# Secondary_MCU_Lidar_Robot.net
KiCad netlist of a schematic drawn in Altium Designer
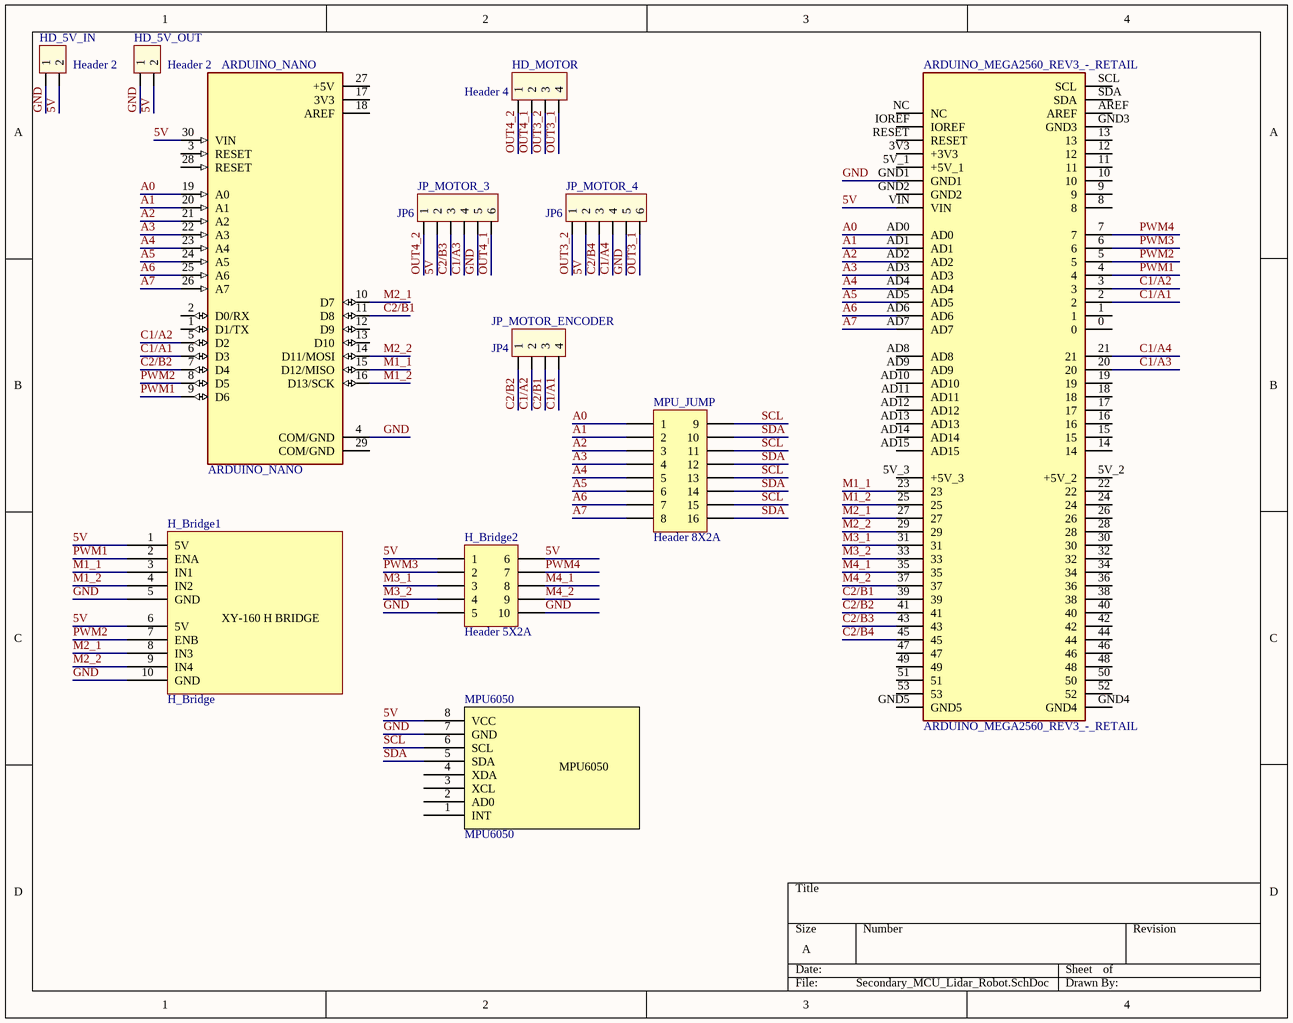
[diagram p0: Secondary_MCU_Lidar_Robot.SchDoc]

(export (version "E")
  (design (tool "Eeschema 10.0.6"))
  (components
    (comp (ref "ARDUINO_MEGA2560_REV3_-_RETAIL")
      (value "ARDUINO_MEGA2560_REV3_-_RETAIL")
      (footprint "ARDUINO_MEGA2560_REV3_-_RETAIL")
      (description "Dev.kit: Arduino; SPI, TWI, UART; ICSP, USB B, pin strips, supply")
      (fields (field (name "MF") "Arduino") (field (name "MP") "ARDUINO MEGA2560 REV3 - RETAIL"))
      (libsource (lib "ARDUINO_MEGA2560_REV3_-_RETAIL") (part "ARDUINO_MEGA2560_REV3_-_RETAIL"))
    )
    (comp (ref "ARDUINO_NANO")
      (value "ARDUINO_NANO")
      (footprint "SHIELD_ARDUINO_NANO")
      (description "ATSAMD21G18A Arduino Nano 33 IoT SAM D ARMÂ® CortexÂ®-M0+ MCU 32-Bit Embedded Evaluation Board")
      (fields (field (name "MP") "ARDUINO NANO") (field (name "MF") "Arduino"))
      (libsource (lib "ARDUINO_NANO") (part "ARDUINO_NANO"))
    )
    (comp (ref "HD_5V_IN")
      (value "Header 2")
      (footprint "HED2T")
      (description "Header 2 (Green)")
      (libsource (lib "syhaunguyen") (part "Hed2"))
    )
    (comp (ref "HD_5V_OUT")
      (value "Header 2")
      (footprint "HED2T")
      (description "Header 2 (Green)")
      (libsource (lib "syhaunguyen") (part "Hed2"))
    )
    (comp (ref "HD_MOTOR")
      (value "Header 4")
      (footprint "HED4T")
      (description "Header 4 (Green)")
      (libsource (lib "syhaunguyen") (part "Hed4"))
    )
    (comp (ref "H_Bridge1")
      (value "H_Bridge")
      (footprint "XY-160D")
      (libsource (lib "Module") (part "Driver H Bridge XY160D"))
    )
    (comp (ref "H_Bridge2")
      (value "Header 5X2A")
      (footprint "HDR2X5_CEN")
      (description "Header, 5-Pin, Dual row")
      (fields (field (name "PUBLISHER") "Altium Limited"))
      (libsource (lib "My library altium") (part "Header 5X2A"))
    )
    (comp (ref "JP_MOTOR_3")
      (value "JP6")
      (footprint "CON6")
      (description "Connector 6")
      (libsource (lib "syhaunguyen") (part "Con6"))
    )
    (comp (ref "JP_MOTOR_4")
      (value "JP6")
      (footprint "CON6")
      (description "Connector 6")
      (libsource (lib "syhaunguyen") (part "Con6"))
    )
    (comp (ref "JP_MOTOR_ENCODER")
      (value "JP4")
      (footprint "CON4")
      (description "Connector 4")
      (libsource (lib "syhaunguyen") (part "Con4"))
    )
    (comp (ref "MPU6050") (value "MPU6050") (footprint "MPU6050") (libsource (lib "Module") (part "MPU6050")))
    (comp (ref "MPU_JUMP")
      (value "Header 8X2A")
      (footprint "HDR2X8_CEN")
      (description "Header, 8-Pin, Dual row")
      (fields (field (name "PUBLISHER") "Altium Limited"))
      (libsource (lib "My library altium") (part "Header 8X2A"))
    )
  )
  (nets
    (net (code "1") (name "/5V") (class "Default")
      (node (ref "ARDUINO_MEGA2560_REV3_-_RETAIL") (pin "VIN") (pinfunction "VIN_VIN") (pintype "passive"))
      (node (ref "ARDUINO_NANO") (pin "30") (pinfunction "VIN_30") (pintype "input"))
      (node (ref "HD_5V_IN") (pin "2") (pinfunction "2_2") (pintype "passive"))
      (node (ref "HD_5V_OUT") (pin "2") (pinfunction "2_2") (pintype "passive"))
      (node (ref "H_Bridge1") (pin "1") (pinfunction "5V_1") (pintype "passive"))
      (node (ref "H_Bridge1") (pin "6") (pinfunction "5V_6") (pintype "passive"))
      (node (ref "H_Bridge2") (pin "1") (pinfunction "1_1") (pintype "passive"))
      (node (ref "H_Bridge2") (pin "6") (pinfunction "6_6") (pintype "passive"))
      (node (ref "JP_MOTOR_3") (pin "2") (pinfunction "2_2") (pintype "passive"))
      (node (ref "JP_MOTOR_4") (pin "2") (pinfunction "2_2") (pintype "passive"))
      (node (ref "MPU6050") (pin "8") (pinfunction "VCC_8") (pintype "passive"))
    )
    (net (code "2") (name "/A0") (class "Default")
      (node (ref "ARDUINO_MEGA2560_REV3_-_RETAIL") (pin "AD0") (pinfunction "AD0_AD0") (pintype "passive"))
      (node (ref "ARDUINO_NANO") (pin "19") (pinfunction "A0_19") (pintype "input"))
      (node (ref "MPU_JUMP") (pin "1") (pinfunction "1_1") (pintype "passive"))
    )
    (net (code "3") (name "/A1") (class "Default")
      (node (ref "ARDUINO_MEGA2560_REV3_-_RETAIL") (pin "AD1") (pinfunction "AD1_AD1") (pintype "passive"))
      (node (ref "ARDUINO_NANO") (pin "20") (pinfunction "A1_20") (pintype "input"))
      (node (ref "MPU_JUMP") (pin "2") (pinfunction "2_2") (pintype "passive"))
    )
    (net (code "4") (name "/A2") (class "Default")
      (node (ref "ARDUINO_MEGA2560_REV3_-_RETAIL") (pin "AD2") (pinfunction "AD2_AD2") (pintype "passive"))
      (node (ref "ARDUINO_NANO") (pin "21") (pinfunction "A2_21") (pintype "input"))
      (node (ref "MPU_JUMP") (pin "3") (pinfunction "3_3") (pintype "passive"))
    )
    (net (code "5") (name "/A3") (class "Default")
      (node (ref "ARDUINO_MEGA2560_REV3_-_RETAIL") (pin "AD3") (pinfunction "AD3_AD3") (pintype "passive"))
      (node (ref "ARDUINO_NANO") (pin "22") (pinfunction "A3_22") (pintype "input"))
      (node (ref "MPU_JUMP") (pin "4") (pinfunction "4_4") (pintype "passive"))
    )
    (net (code "6") (name "/A4") (class "Default")
      (node (ref "ARDUINO_MEGA2560_REV3_-_RETAIL") (pin "AD4") (pinfunction "AD4_AD4") (pintype "passive"))
      (node (ref "ARDUINO_NANO") (pin "23") (pinfunction "A4_23") (pintype "input"))
      (node (ref "MPU_JUMP") (pin "5") (pinfunction "5_5") (pintype "passive"))
    )
    (net (code "7") (name "/A5") (class "Default")
      (node (ref "ARDUINO_MEGA2560_REV3_-_RETAIL") (pin "AD5") (pinfunction "AD5_AD5") (pintype "passive"))
      (node (ref "ARDUINO_NANO") (pin "24") (pinfunction "A5_24") (pintype "input"))
      (node (ref "MPU_JUMP") (pin "6") (pinfunction "6_6") (pintype "passive"))
    )
    (net (code "8") (name "/A6") (class "Default")
      (node (ref "ARDUINO_MEGA2560_REV3_-_RETAIL") (pin "AD6") (pinfunction "AD6_AD6") (pintype "passive"))
      (node (ref "ARDUINO_NANO") (pin "25") (pinfunction "A6_25") (pintype "input"))
      (node (ref "MPU_JUMP") (pin "7") (pinfunction "7_7") (pintype "passive"))
    )
    (net (code "9") (name "/A7") (class "Default")
      (node (ref "ARDUINO_MEGA2560_REV3_-_RETAIL") (pin "AD7") (pinfunction "AD7_AD7") (pintype "passive"))
      (node (ref "ARDUINO_NANO") (pin "26") (pinfunction "A7_26") (pintype "input"))
      (node (ref "MPU_JUMP") (pin "8") (pinfunction "8_8") (pintype "passive"))
    )
    (net (code "10") (name "/C1{slash}A1") (class "Default")
      (node (ref "ARDUINO_MEGA2560_REV3_-_RETAIL") (pin "2") (pinfunction "2_2") (pintype "passive"))
      (node (ref "ARDUINO_NANO") (pin "6") (pinfunction "D3_6") (pintype "bidirectional"))
      (node (ref "JP_MOTOR_ENCODER") (pin "4") (pinfunction "4_4") (pintype "passive"))
    )
    (net (code "11") (name "/C1{slash}A2") (class "Default")
      (node (ref "ARDUINO_MEGA2560_REV3_-_RETAIL") (pin "3") (pinfunction "3_3") (pintype "passive"))
      (node (ref "ARDUINO_NANO") (pin "5") (pinfunction "D2_5") (pintype "bidirectional"))
      (node (ref "JP_MOTOR_ENCODER") (pin "2") (pinfunction "2_2") (pintype "passive"))
    )
    (net (code "12") (name "/C1{slash}A3") (class "Default")
      (node (ref "ARDUINO_MEGA2560_REV3_-_RETAIL") (pin "20") (pinfunction "20_20") (pintype "passive"))
      (node (ref "JP_MOTOR_3") (pin "4") (pinfunction "4_4") (pintype "passive"))
    )
    (net (code "13") (name "/C1{slash}A4") (class "Default")
      (node (ref "ARDUINO_MEGA2560_REV3_-_RETAIL") (pin "21") (pinfunction "21_21") (pintype "passive"))
      (node (ref "JP_MOTOR_4") (pin "4") (pinfunction "4_4") (pintype "passive"))
    )
    (net (code "14") (name "/C2{slash}B1") (class "Default")
      (node (ref "ARDUINO_MEGA2560_REV3_-_RETAIL") (pin "39") (pinfunction "39_39") (pintype "passive"))
      (node (ref "ARDUINO_NANO") (pin "11") (pinfunction "D8_11") (pintype "bidirectional"))
      (node (ref "JP_MOTOR_ENCODER") (pin "3") (pinfunction "3_3") (pintype "passive"))
    )
    (net (code "15") (name "/C2{slash}B2") (class "Default")
      (node (ref "ARDUINO_MEGA2560_REV3_-_RETAIL") (pin "41") (pinfunction "41_41") (pintype "passive"))
      (node (ref "ARDUINO_NANO") (pin "7") (pinfunction "D4_7") (pintype "bidirectional"))
      (node (ref "JP_MOTOR_ENCODER") (pin "1") (pinfunction "1_1") (pintype "passive"))
    )
    (net (code "16") (name "/C2{slash}B3") (class "Default")
      (node (ref "ARDUINO_MEGA2560_REV3_-_RETAIL") (pin "43") (pinfunction "43_43") (pintype "passive"))
      (node (ref "JP_MOTOR_3") (pin "3") (pinfunction "3_3") (pintype "passive"))
    )
    (net (code "17") (name "/C2{slash}B4") (class "Default")
      (node (ref "ARDUINO_MEGA2560_REV3_-_RETAIL") (pin "45") (pinfunction "45_45") (pintype "passive"))
      (node (ref "JP_MOTOR_4") (pin "3") (pinfunction "3_3") (pintype "passive"))
    )
    (net (code "18") (name "/GND") (class "Default")
      (node (ref "ARDUINO_MEGA2560_REV3_-_RETAIL") (pin "GND1") (pinfunction "GND1_GND1") (pintype "passive"))
      (node (ref "ARDUINO_NANO") (pin "4") (pinfunction "COM/GND_4") (pintype "power_in"))
      (node (ref "HD_5V_IN") (pin "1") (pinfunction "1_1") (pintype "passive"))
      (node (ref "HD_5V_OUT") (pin "1") (pinfunction "1_1") (pintype "passive"))
      (node (ref "H_Bridge1") (pin "10") (pinfunction "GND_10") (pintype "passive"))
      (node (ref "H_Bridge1") (pin "5") (pinfunction "GND_5") (pintype "passive"))
      (node (ref "H_Bridge2") (pin "10") (pinfunction "10_10") (pintype "passive"))
      (node (ref "H_Bridge2") (pin "5") (pinfunction "5_5") (pintype "passive"))
      (node (ref "JP_MOTOR_3") (pin "5") (pinfunction "5_5") (pintype "passive"))
      (node (ref "JP_MOTOR_4") (pin "5") (pinfunction "5_5") (pintype "passive"))
      (node (ref "MPU6050") (pin "7") (pinfunction "GND_7") (pintype "passive"))
    )
    (net (code "19") (name "/M1_1") (class "Default")
      (node (ref "ARDUINO_MEGA2560_REV3_-_RETAIL") (pin "23") (pinfunction "23_23") (pintype "passive"))
      (node (ref "ARDUINO_NANO") (pin "15") (pinfunction "D12/MISO_15") (pintype "bidirectional"))
      (node (ref "H_Bridge1") (pin "3") (pinfunction "IN1_3") (pintype "passive"))
    )
    (net (code "20") (name "/M1_2") (class "Default")
      (node (ref "ARDUINO_MEGA2560_REV3_-_RETAIL") (pin "25") (pinfunction "25_25") (pintype "passive"))
      (node (ref "ARDUINO_NANO") (pin "16") (pinfunction "D13/SCK_16") (pintype "bidirectional"))
      (node (ref "H_Bridge1") (pin "4") (pinfunction "IN2_4") (pintype "passive"))
    )
    (net (code "21") (name "/M2_1") (class "Default")
      (node (ref "ARDUINO_MEGA2560_REV3_-_RETAIL") (pin "27") (pinfunction "27_27") (pintype "passive"))
      (node (ref "ARDUINO_NANO") (pin "10") (pinfunction "D7_10") (pintype "bidirectional"))
      (node (ref "H_Bridge1") (pin "8") (pinfunction "IN3_8") (pintype "passive"))
    )
    (net (code "22") (name "/M2_2") (class "Default")
      (node (ref "ARDUINO_MEGA2560_REV3_-_RETAIL") (pin "29") (pinfunction "29_29") (pintype "passive"))
      (node (ref "ARDUINO_NANO") (pin "14") (pinfunction "D11/MOSI_14") (pintype "bidirectional"))
      (node (ref "H_Bridge1") (pin "9") (pinfunction "IN4_9") (pintype "passive"))
    )
    (net (code "23") (name "/M3_1") (class "Default")
      (node (ref "ARDUINO_MEGA2560_REV3_-_RETAIL") (pin "31") (pinfunction "31_31") (pintype "passive"))
      (node (ref "H_Bridge2") (pin "3") (pinfunction "3_3") (pintype "passive"))
    )
    (net (code "24") (name "/M3_2") (class "Default")
      (node (ref "ARDUINO_MEGA2560_REV3_-_RETAIL") (pin "33") (pinfunction "33_33") (pintype "passive"))
      (node (ref "H_Bridge2") (pin "4") (pinfunction "4_4") (pintype "passive"))
    )
    (net (code "25") (name "/M4_1") (class "Default")
      (node (ref "ARDUINO_MEGA2560_REV3_-_RETAIL") (pin "35") (pinfunction "35_35") (pintype "passive"))
      (node (ref "H_Bridge2") (pin "8") (pinfunction "8_8") (pintype "passive"))
    )
    (net (code "26") (name "/M4_2") (class "Default")
      (node (ref "ARDUINO_MEGA2560_REV3_-_RETAIL") (pin "37") (pinfunction "37_37") (pintype "passive"))
      (node (ref "H_Bridge2") (pin "9") (pinfunction "9_9") (pintype "passive"))
    )
    (net (code "27") (name "/OUT3_1") (class "Default")
      (node (ref "HD_MOTOR") (pin "4") (pinfunction "4_4") (pintype "passive"))
      (node (ref "JP_MOTOR_4") (pin "6") (pinfunction "6_6") (pintype "passive"))
    )
    (net (code "28") (name "/OUT3_2") (class "Default")
      (node (ref "HD_MOTOR") (pin "3") (pinfunction "3_3") (pintype "passive"))
      (node (ref "JP_MOTOR_4") (pin "1") (pinfunction "1_1") (pintype "passive"))
    )
    (net (code "29") (name "/OUT4_1") (class "Default")
      (node (ref "HD_MOTOR") (pin "2") (pinfunction "2_2") (pintype "passive"))
      (node (ref "JP_MOTOR_3") (pin "6") (pinfunction "6_6") (pintype "passive"))
    )
    (net (code "30") (name "/OUT4_2") (class "Default")
      (node (ref "HD_MOTOR") (pin "1") (pinfunction "1_1") (pintype "passive"))
      (node (ref "JP_MOTOR_3") (pin "1") (pinfunction "1_1") (pintype "passive"))
    )
    (net (code "31") (name "/PWM1") (class "Default")
      (node (ref "ARDUINO_MEGA2560_REV3_-_RETAIL") (pin "4") (pinfunction "4_4") (pintype "passive"))
      (node (ref "ARDUINO_NANO") (pin "9") (pinfunction "D6_9") (pintype "bidirectional"))
      (node (ref "H_Bridge1") (pin "2") (pinfunction "ENA_2") (pintype "passive"))
    )
    (net (code "32") (name "/PWM2") (class "Default")
      (node (ref "ARDUINO_MEGA2560_REV3_-_RETAIL") (pin "5") (pinfunction "5_5") (pintype "passive"))
      (node (ref "ARDUINO_NANO") (pin "8") (pinfunction "D5_8") (pintype "bidirectional"))
      (node (ref "H_Bridge1") (pin "7") (pinfunction "ENB_7") (pintype "passive"))
    )
    (net (code "33") (name "/PWM3") (class "Default")
      (node (ref "ARDUINO_MEGA2560_REV3_-_RETAIL") (pin "6") (pinfunction "6_6") (pintype "passive"))
      (node (ref "H_Bridge2") (pin "2") (pinfunction "2_2") (pintype "passive"))
    )
    (net (code "34") (name "/PWM4") (class "Default")
      (node (ref "ARDUINO_MEGA2560_REV3_-_RETAIL") (pin "7") (pinfunction "7_7") (pintype "passive"))
      (node (ref "H_Bridge2") (pin "7") (pinfunction "7_7") (pintype "passive"))
    )
    (net (code "35") (name "/SCL") (class "Default")
      (node (ref "MPU6050") (pin "6") (pinfunction "SCL_6") (pintype "passive"))
      (node (ref "MPU_JUMP") (pin "11") (pinfunction "11_11") (pintype "passive"))
      (node (ref "MPU_JUMP") (pin "13") (pinfunction "13_13") (pintype "passive"))
      (node (ref "MPU_JUMP") (pin "15") (pinfunction "15_15") (pintype "passive"))
      (node (ref "MPU_JUMP") (pin "9") (pinfunction "9_9") (pintype "passive"))
    )
    (net (code "36") (name "/SDA") (class "Default")
      (node (ref "MPU6050") (pin "5") (pinfunction "SDA_5") (pintype "passive"))
      (node (ref "MPU_JUMP") (pin "10") (pinfunction "10_10") (pintype "passive"))
      (node (ref "MPU_JUMP") (pin "12") (pinfunction "12_12") (pintype "passive"))
      (node (ref "MPU_JUMP") (pin "14") (pinfunction "14_14") (pintype "passive"))
      (node (ref "MPU_JUMP") (pin "16") (pinfunction "16_16") (pintype "passive"))
    )
    (net (code "37") (name "unconnected-(ARDUINO_MEGA2560_REV3_-_RETAIL-+3V3-Pad3V3)") (class "Default")
      (node (ref "ARDUINO_MEGA2560_REV3_-_RETAIL") (pin "3V3") (pinfunction "+3V3_3V3") (pintype "passive"))
    )
    (net (code "38") (name "unconnected-(ARDUINO_MEGA2560_REV3_-_RETAIL-+5V_1-Pad5V_1)") (class "Default")
      (node (ref "ARDUINO_MEGA2560_REV3_-_RETAIL") (pin "5V_1") (pinfunction "+5V_1_5V_1") (pintype "passive"))
    )
    (net (code "39") (name "unconnected-(ARDUINO_MEGA2560_REV3_-_RETAIL-+5V_2-Pad5V_2)") (class "Default")
      (node (ref "ARDUINO_MEGA2560_REV3_-_RETAIL") (pin "5V_2") (pinfunction "+5V_2_5V_2") (pintype "passive"))
    )
    (net (code "40") (name "unconnected-(ARDUINO_MEGA2560_REV3_-_RETAIL-+5V_3-Pad5V_3)") (class "Default")
      (node (ref "ARDUINO_MEGA2560_REV3_-_RETAIL") (pin "5V_3") (pinfunction "+5V_3_5V_3") (pintype "passive"))
    )
    (net (code "41") (name "unconnected-(ARDUINO_MEGA2560_REV3_-_RETAIL-Pad0)") (class "Default")
      (node (ref "ARDUINO_MEGA2560_REV3_-_RETAIL") (pin "0") (pinfunction "0_0") (pintype "passive"))
    )
    (net (code "42") (name "unconnected-(ARDUINO_MEGA2560_REV3_-_RETAIL-Pad1)") (class "Default")
      (node (ref "ARDUINO_MEGA2560_REV3_-_RETAIL") (pin "1") (pinfunction "1_1") (pintype "passive"))
    )
    (net (code "43") (name "unconnected-(ARDUINO_MEGA2560_REV3_-_RETAIL-Pad8)") (class "Default")
      (node (ref "ARDUINO_MEGA2560_REV3_-_RETAIL") (pin "8") (pinfunction "8_8") (pintype "passive"))
    )
    (net (code "44") (name "unconnected-(ARDUINO_MEGA2560_REV3_-_RETAIL-Pad9)") (class "Default")
      (node (ref "ARDUINO_MEGA2560_REV3_-_RETAIL") (pin "9") (pinfunction "9_9") (pintype "passive"))
    )
    (net (code "45") (name "unconnected-(ARDUINO_MEGA2560_REV3_-_RETAIL-Pad10)") (class "Default")
      (node (ref "ARDUINO_MEGA2560_REV3_-_RETAIL") (pin "10") (pinfunction "10_10") (pintype "passive"))
    )
    (net (code "46") (name "unconnected-(ARDUINO_MEGA2560_REV3_-_RETAIL-Pad11)") (class "Default")
      (node (ref "ARDUINO_MEGA2560_REV3_-_RETAIL") (pin "11") (pinfunction "11_11") (pintype "passive"))
    )
    (net (code "47") (name "unconnected-(ARDUINO_MEGA2560_REV3_-_RETAIL-Pad12)") (class "Default")
      (node (ref "ARDUINO_MEGA2560_REV3_-_RETAIL") (pin "12") (pinfunction "12_12") (pintype "passive"))
    )
    (net (code "48") (name "unconnected-(ARDUINO_MEGA2560_REV3_-_RETAIL-Pad13)") (class "Default")
      (node (ref "ARDUINO_MEGA2560_REV3_-_RETAIL") (pin "13") (pinfunction "13_13") (pintype "passive"))
    )
    (net (code "49") (name "unconnected-(ARDUINO_MEGA2560_REV3_-_RETAIL-Pad14)") (class "Default")
      (node (ref "ARDUINO_MEGA2560_REV3_-_RETAIL") (pin "14") (pinfunction "14_14") (pintype "passive"))
    )
    (net (code "50") (name "unconnected-(ARDUINO_MEGA2560_REV3_-_RETAIL-Pad15)") (class "Default")
      (node (ref "ARDUINO_MEGA2560_REV3_-_RETAIL") (pin "15") (pinfunction "15_15") (pintype "passive"))
    )
    (net (code "51") (name "unconnected-(ARDUINO_MEGA2560_REV3_-_RETAIL-Pad16)") (class "Default")
      (node (ref "ARDUINO_MEGA2560_REV3_-_RETAIL") (pin "16") (pinfunction "16_16") (pintype "passive"))
    )
    (net (code "52") (name "unconnected-(ARDUINO_MEGA2560_REV3_-_RETAIL-Pad17)") (class "Default")
      (node (ref "ARDUINO_MEGA2560_REV3_-_RETAIL") (pin "17") (pinfunction "17_17") (pintype "passive"))
    )
    (net (code "53") (name "unconnected-(ARDUINO_MEGA2560_REV3_-_RETAIL-Pad18)") (class "Default")
      (node (ref "ARDUINO_MEGA2560_REV3_-_RETAIL") (pin "18") (pinfunction "18_18") (pintype "passive"))
    )
    (net (code "54") (name "unconnected-(ARDUINO_MEGA2560_REV3_-_RETAIL-Pad19)") (class "Default")
      (node (ref "ARDUINO_MEGA2560_REV3_-_RETAIL") (pin "19") (pinfunction "19_19") (pintype "passive"))
    )
    (net (code "55") (name "unconnected-(ARDUINO_MEGA2560_REV3_-_RETAIL-Pad22)") (class "Default")
      (node (ref "ARDUINO_MEGA2560_REV3_-_RETAIL") (pin "22") (pinfunction "22_22") (pintype "passive"))
    )
    (net (code "56") (name "unconnected-(ARDUINO_MEGA2560_REV3_-_RETAIL-Pad24)") (class "Default")
      (node (ref "ARDUINO_MEGA2560_REV3_-_RETAIL") (pin "24") (pinfunction "24_24") (pintype "passive"))
    )
    (net (code "57") (name "unconnected-(ARDUINO_MEGA2560_REV3_-_RETAIL-Pad26)") (class "Default")
      (node (ref "ARDUINO_MEGA2560_REV3_-_RETAIL") (pin "26") (pinfunction "26_26") (pintype "passive"))
    )
    (net (code "58") (name "unconnected-(ARDUINO_MEGA2560_REV3_-_RETAIL-Pad28)") (class "Default")
      (node (ref "ARDUINO_MEGA2560_REV3_-_RETAIL") (pin "28") (pinfunction "28_28") (pintype "passive"))
    )
    (net (code "59") (name "unconnected-(ARDUINO_MEGA2560_REV3_-_RETAIL-Pad30)") (class "Default")
      (node (ref "ARDUINO_MEGA2560_REV3_-_RETAIL") (pin "30") (pinfunction "30_30") (pintype "passive"))
    )
    (net (code "60") (name "unconnected-(ARDUINO_MEGA2560_REV3_-_RETAIL-Pad32)") (class "Default")
      (node (ref "ARDUINO_MEGA2560_REV3_-_RETAIL") (pin "32") (pinfunction "32_32") (pintype "passive"))
    )
    (net (code "61") (name "unconnected-(ARDUINO_MEGA2560_REV3_-_RETAIL-Pad34)") (class "Default")
      (node (ref "ARDUINO_MEGA2560_REV3_-_RETAIL") (pin "34") (pinfunction "34_34") (pintype "passive"))
    )
    (net (code "62") (name "unconnected-(ARDUINO_MEGA2560_REV3_-_RETAIL-Pad36)") (class "Default")
      (node (ref "ARDUINO_MEGA2560_REV3_-_RETAIL") (pin "36") (pinfunction "36_36") (pintype "passive"))
    )
    (net (code "63") (name "unconnected-(ARDUINO_MEGA2560_REV3_-_RETAIL-Pad38)") (class "Default")
      (node (ref "ARDUINO_MEGA2560_REV3_-_RETAIL") (pin "38") (pinfunction "38_38") (pintype "passive"))
    )
    (net (code "64") (name "unconnected-(ARDUINO_MEGA2560_REV3_-_RETAIL-Pad40)") (class "Default")
      (node (ref "ARDUINO_MEGA2560_REV3_-_RETAIL") (pin "40") (pinfunction "40_40") (pintype "passive"))
    )
    (net (code "65") (name "unconnected-(ARDUINO_MEGA2560_REV3_-_RETAIL-Pad42)") (class "Default")
      (node (ref "ARDUINO_MEGA2560_REV3_-_RETAIL") (pin "42") (pinfunction "42_42") (pintype "passive"))
    )
    (net (code "66") (name "unconnected-(ARDUINO_MEGA2560_REV3_-_RETAIL-Pad44)") (class "Default")
      (node (ref "ARDUINO_MEGA2560_REV3_-_RETAIL") (pin "44") (pinfunction "44_44") (pintype "passive"))
    )
    (net (code "67") (name "unconnected-(ARDUINO_MEGA2560_REV3_-_RETAIL-Pad46)") (class "Default")
      (node (ref "ARDUINO_MEGA2560_REV3_-_RETAIL") (pin "46") (pinfunction "46_46") (pintype "passive"))
    )
    (net (code "68") (name "unconnected-(ARDUINO_MEGA2560_REV3_-_RETAIL-Pad47)") (class "Default")
      (node (ref "ARDUINO_MEGA2560_REV3_-_RETAIL") (pin "47") (pinfunction "47_47") (pintype "passive"))
    )
    (net (code "69") (name "unconnected-(ARDUINO_MEGA2560_REV3_-_RETAIL-Pad48)") (class "Default")
      (node (ref "ARDUINO_MEGA2560_REV3_-_RETAIL") (pin "48") (pinfunction "48_48") (pintype "passive"))
    )
    (net (code "70") (name "unconnected-(ARDUINO_MEGA2560_REV3_-_RETAIL-Pad49)") (class "Default")
      (node (ref "ARDUINO_MEGA2560_REV3_-_RETAIL") (pin "49") (pinfunction "49_49") (pintype "passive"))
    )
    (net (code "71") (name "unconnected-(ARDUINO_MEGA2560_REV3_-_RETAIL-Pad50)") (class "Default")
      (node (ref "ARDUINO_MEGA2560_REV3_-_RETAIL") (pin "50") (pinfunction "50_50") (pintype "passive"))
    )
    (net (code "72") (name "unconnected-(ARDUINO_MEGA2560_REV3_-_RETAIL-Pad51)") (class "Default")
      (node (ref "ARDUINO_MEGA2560_REV3_-_RETAIL") (pin "51") (pinfunction "51_51") (pintype "passive"))
    )
    (net (code "73") (name "unconnected-(ARDUINO_MEGA2560_REV3_-_RETAIL-Pad52)") (class "Default")
      (node (ref "ARDUINO_MEGA2560_REV3_-_RETAIL") (pin "52") (pinfunction "52_52") (pintype "passive"))
    )
    (net (code "74") (name "unconnected-(ARDUINO_MEGA2560_REV3_-_RETAIL-Pad53)") (class "Default")
      (node (ref "ARDUINO_MEGA2560_REV3_-_RETAIL") (pin "53") (pinfunction "53_53") (pintype "passive"))
    )
    (net (code "75") (name "unconnected-(ARDUINO_MEGA2560_REV3_-_RETAIL-PadAD8)") (class "Default")
      (node (ref "ARDUINO_MEGA2560_REV3_-_RETAIL") (pin "AD8") (pinfunction "AD8_AD8") (pintype "passive"))
    )
    (net (code "76") (name "unconnected-(ARDUINO_MEGA2560_REV3_-_RETAIL-PadAD9)") (class "Default")
      (node (ref "ARDUINO_MEGA2560_REV3_-_RETAIL") (pin "AD9") (pinfunction "AD9_AD9") (pintype "passive"))
    )
    (net (code "77") (name "unconnected-(ARDUINO_MEGA2560_REV3_-_RETAIL-PadAD10)") (class "Default")
      (node (ref "ARDUINO_MEGA2560_REV3_-_RETAIL") (pin "AD10") (pinfunction "AD10_AD10") (pintype "passive"))
    )
    (net (code "78") (name "unconnected-(ARDUINO_MEGA2560_REV3_-_RETAIL-PadAD11)") (class "Default")
      (node (ref "ARDUINO_MEGA2560_REV3_-_RETAIL") (pin "AD11") (pinfunction "AD11_AD11") (pintype "passive"))
    )
    (net (code "79") (name "unconnected-(ARDUINO_MEGA2560_REV3_-_RETAIL-PadAD12)") (class "Default")
      (node (ref "ARDUINO_MEGA2560_REV3_-_RETAIL") (pin "AD12") (pinfunction "AD12_AD12") (pintype "passive"))
    )
    (net (code "80") (name "unconnected-(ARDUINO_MEGA2560_REV3_-_RETAIL-PadAD13)") (class "Default")
      (node (ref "ARDUINO_MEGA2560_REV3_-_RETAIL") (pin "AD13") (pinfunction "AD13_AD13") (pintype "passive"))
    )
    (net (code "81") (name "unconnected-(ARDUINO_MEGA2560_REV3_-_RETAIL-PadAD14)") (class "Default")
      (node (ref "ARDUINO_MEGA2560_REV3_-_RETAIL") (pin "AD14") (pinfunction "AD14_AD14") (pintype "passive"))
    )
    (net (code "82") (name "unconnected-(ARDUINO_MEGA2560_REV3_-_RETAIL-PadAD15)") (class "Default")
      (node (ref "ARDUINO_MEGA2560_REV3_-_RETAIL") (pin "AD15") (pinfunction "AD15_AD15") (pintype "passive"))
    )
    (net (code "83") (name "unconnected-(ARDUINO_MEGA2560_REV3_-_RETAIL-PadAREF)") (class "Default")
      (node (ref "ARDUINO_MEGA2560_REV3_-_RETAIL") (pin "AREF") (pinfunction "AREF_AREF") (pintype "passive"))
    )
    (net (code "84") (name "unconnected-(ARDUINO_MEGA2560_REV3_-_RETAIL-PadGND2)") (class "Default")
      (node (ref "ARDUINO_MEGA2560_REV3_-_RETAIL") (pin "GND2") (pinfunction "GND2_GND2") (pintype "passive"))
    )
    (net (code "85") (name "unconnected-(ARDUINO_MEGA2560_REV3_-_RETAIL-PadGND3)") (class "Default")
      (node (ref "ARDUINO_MEGA2560_REV3_-_RETAIL") (pin "GND3") (pinfunction "GND3_GND3") (pintype "passive"))
    )
    (net (code "86") (name "unconnected-(ARDUINO_MEGA2560_REV3_-_RETAIL-PadGND4)") (class "Default")
      (node (ref "ARDUINO_MEGA2560_REV3_-_RETAIL") (pin "GND4") (pinfunction "GND4_GND4") (pintype "passive"))
    )
    (net (code "87") (name "unconnected-(ARDUINO_MEGA2560_REV3_-_RETAIL-PadGND5)") (class "Default")
      (node (ref "ARDUINO_MEGA2560_REV3_-_RETAIL") (pin "GND5") (pinfunction "GND5_GND5") (pintype "passive"))
    )
    (net (code "88") (name "unconnected-(ARDUINO_MEGA2560_REV3_-_RETAIL-PadIOREF)") (class "Default")
      (node (ref "ARDUINO_MEGA2560_REV3_-_RETAIL") (pin "IOREF") (pinfunction "IOREF_IOREF") (pintype "passive"))
    )
    (net (code "89") (name "unconnected-(ARDUINO_MEGA2560_REV3_-_RETAIL-PadNC)") (class "Default")
      (node (ref "ARDUINO_MEGA2560_REV3_-_RETAIL") (pin "NC") (pinfunction "NC_NC") (pintype "passive"))
    )
    (net (code "90") (name "unconnected-(ARDUINO_MEGA2560_REV3_-_RETAIL-PadRESET)") (class "Default")
      (node (ref "ARDUINO_MEGA2560_REV3_-_RETAIL") (pin "RESET") (pinfunction "RESET_RESET") (pintype "passive"))
    )
    (net (code "91") (name "unconnected-(ARDUINO_MEGA2560_REV3_-_RETAIL-PadSCL)") (class "Default")
      (node (ref "ARDUINO_MEGA2560_REV3_-_RETAIL") (pin "SCL") (pinfunction "SCL_SCL") (pintype "passive"))
    )
    (net (code "92") (name "unconnected-(ARDUINO_MEGA2560_REV3_-_RETAIL-PadSDA)") (class "Default")
      (node (ref "ARDUINO_MEGA2560_REV3_-_RETAIL") (pin "SDA") (pinfunction "SDA_SDA") (pintype "passive"))
    )
    (net (code "93") (name "unconnected-(ARDUINO_NANO-+5V-Pad27)") (class "Default")
      (node (ref "ARDUINO_NANO") (pin "27") (pinfunction "+5V_27") (pintype "power_in"))
    )
    (net (code "94") (name "unconnected-(ARDUINO_NANO-3V3-Pad17)") (class "Default")
      (node (ref "ARDUINO_NANO") (pin "17") (pinfunction "3V3_17") (pintype "power_in"))
    )
    (net (code "95") (name "unconnected-(ARDUINO_NANO-AREF-Pad18)") (class "Default")
      (node (ref "ARDUINO_NANO") (pin "18") (pinfunction "AREF_18") (pintype "power_in"))
    )
    (net (code "96") (name "unconnected-(ARDUINO_NANO-COM{slash}GND-Pad29)") (class "Default")
      (node (ref "ARDUINO_NANO") (pin "29") (pinfunction "COM/GND_29") (pintype "power_in"))
    )
    (net (code "97") (name "unconnected-(ARDUINO_NANO-D0{slash}RX-Pad2)") (class "Default")
      (node (ref "ARDUINO_NANO") (pin "2") (pinfunction "D0/RX_2") (pintype "bidirectional"))
    )
    (net (code "98") (name "unconnected-(ARDUINO_NANO-D1{slash}TX-Pad1)") (class "Default")
      (node (ref "ARDUINO_NANO") (pin "1") (pinfunction "D1/TX_1") (pintype "bidirectional"))
    )
    (net (code "99") (name "unconnected-(ARDUINO_NANO-D9-Pad12)") (class "Default")
      (node (ref "ARDUINO_NANO") (pin "12") (pinfunction "D9_12") (pintype "bidirectional"))
    )
    (net (code "100") (name "unconnected-(ARDUINO_NANO-D10-Pad13)") (class "Default")
      (node (ref "ARDUINO_NANO") (pin "13") (pinfunction "D10_13") (pintype "bidirectional"))
    )
    (net (code "101") (name "unconnected-(ARDUINO_NANO-RESET-Pad3)") (class "Default")
      (node (ref "ARDUINO_NANO") (pin "3") (pinfunction "RESET_3") (pintype "input"))
    )
    (net (code "102") (name "unconnected-(ARDUINO_NANO-RESET-Pad28)") (class "Default")
      (node (ref "ARDUINO_NANO") (pin "28") (pinfunction "RESET_28") (pintype "input"))
    )
    (net (code "103") (name "unconnected-(MPU6050-AD0-Pad2)") (class "Default")
      (node (ref "MPU6050") (pin "2") (pinfunction "AD0_2") (pintype "passive"))
    )
    (net (code "104") (name "unconnected-(MPU6050-INT-Pad1)") (class "Default")
      (node (ref "MPU6050") (pin "1") (pinfunction "INT_1") (pintype "passive"))
    )
    (net (code "105") (name "unconnected-(MPU6050-XCL-Pad3)") (class "Default")
      (node (ref "MPU6050") (pin "3") (pinfunction "XCL_3") (pintype "passive"))
    )
    (net (code "106") (name "unconnected-(MPU6050-XDA-Pad4)") (class "Default")
      (node (ref "MPU6050") (pin "4") (pinfunction "XDA_4") (pintype "passive"))
    )
  )
)
